# 32u4_macropad.net
KiCad netlist of a schematic drawn in EAGLE
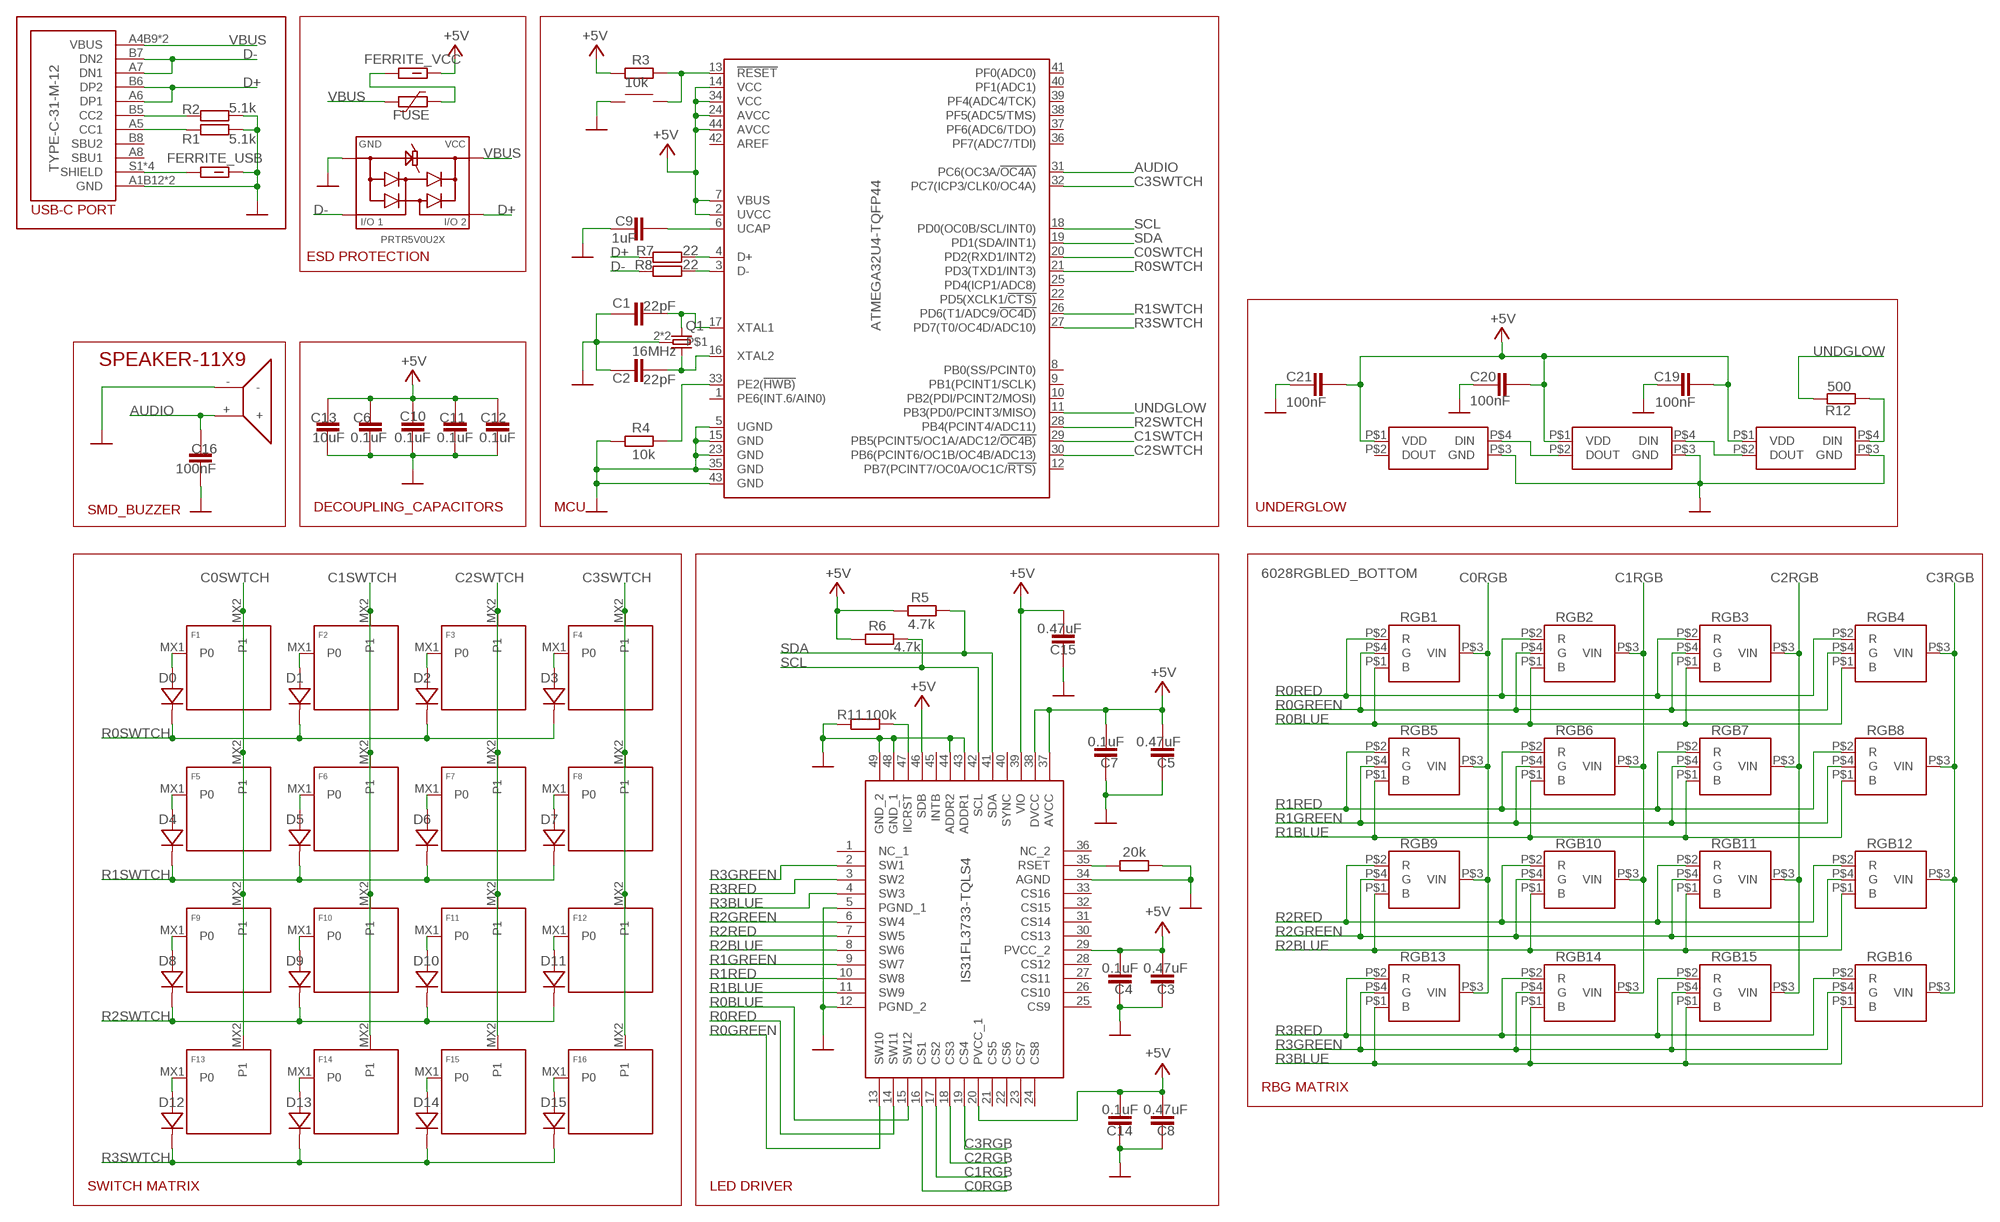
[diagram p0: schematic, sheet 1]

(export (version "E")
  (design (tool "Eeschema 10.0.6"))
  (components
    (comp (ref "C1")
      (value "22pF")
      (footprint "eagle-import:C0603")
      (libsource (lib "eagle-import") (part "CAPACITOR-0603"))
    )
    (comp (ref "C2")
      (value "22pF")
      (footprint "eagle-import:C0603")
      (libsource (lib "eagle-import") (part "CAPACITOR-0603"))
    )
    (comp (ref "C3")
      (value "0.47uF")
      (footprint "eagle-import:C0603")
      (libsource (lib "eagle-import") (part "CAPACITOR-0603"))
    )
    (comp (ref "C4")
      (value "0.1uF")
      (footprint "eagle-import:C0603")
      (libsource (lib "eagle-import") (part "CAPACITOR-0603"))
    )
    (comp (ref "C5")
      (value "0.47uF")
      (footprint "eagle-import:C0603")
      (libsource (lib "eagle-import") (part "CAPACITOR-0603"))
    )
    (comp (ref "C6")
      (value "0.1uF")
      (footprint "eagle-import:C0603")
      (libsource (lib "eagle-import") (part "CAPACITOR-0603"))
    )
    (comp (ref "C7")
      (value "0.1uF")
      (footprint "eagle-import:C0603")
      (libsource (lib "eagle-import") (part "CAPACITOR-0603"))
    )
    (comp (ref "C8")
      (value "0.47uF")
      (footprint "eagle-import:C0603")
      (libsource (lib "eagle-import") (part "CAPACITOR-0603"))
    )
    (comp (ref "C9")
      (value "1uF")
      (footprint "eagle-import:C0603")
      (libsource (lib "eagle-import") (part "CAPACITOR-0603"))
    )
    (comp (ref "C10")
      (value "0.1uF")
      (footprint "eagle-import:C0603")
      (libsource (lib "eagle-import") (part "CAPACITOR-0603"))
    )
    (comp (ref "C11")
      (value "0.1uF")
      (footprint "eagle-import:C0603")
      (libsource (lib "eagle-import") (part "CAPACITOR-0603"))
    )
    (comp (ref "C12")
      (value "0.1uF")
      (footprint "eagle-import:C0603")
      (libsource (lib "eagle-import") (part "CAPACITOR-0603"))
    )
    (comp (ref "C13")
      (value "10uF")
      (footprint "eagle-import:C0603")
      (libsource (lib "eagle-import") (part "CAPACITOR-0603"))
    )
    (comp (ref "C14")
      (value "0.1uF")
      (footprint "eagle-import:C0603")
      (libsource (lib "eagle-import") (part "CAPACITOR-0603"))
    )
    (comp (ref "C15")
      (value "0.47uF")
      (footprint "eagle-import:C0603")
      (libsource (lib "eagle-import") (part "CAPACITOR-0603"))
    )
    (comp (ref "C16")
      (value "100nF")
      (footprint "eagle-import:C0603")
      (libsource (lib "eagle-import") (part "CAPACITOR-0603"))
    )
    (comp (ref "C19")
      (value "100nF")
      (footprint "eagle-import:C0603")
      (libsource (lib "eagle-import") (part "CAPACITOR-0603"))
    )
    (comp (ref "C20")
      (value "100nF")
      (footprint "eagle-import:C0603")
      (libsource (lib "eagle-import") (part "CAPACITOR-0603"))
    )
    (comp (ref "C21")
      (value "100nF")
      (footprint "eagle-import:C0603")
      (libsource (lib "eagle-import") (part "CAPACITOR-0603"))
    )
    (comp (ref "D0")
      (value "DIODE-SOD-123")
      (footprint "eagle-import:SOD-123")
      (libsource (lib "eagle-import") (part "DIODE-SOD-123"))
    )
    (comp (ref "D1")
      (value "DIODE-SOD-123")
      (footprint "eagle-import:SOD-123")
      (libsource (lib "eagle-import") (part "DIODE-SOD-123"))
    )
    (comp (ref "D2")
      (value "DIODE-SOD-123")
      (footprint "eagle-import:SOD-123")
      (libsource (lib "eagle-import") (part "DIODE-SOD-123"))
    )
    (comp (ref "D3")
      (value "DIODE-SOD-123")
      (footprint "eagle-import:SOD-123")
      (libsource (lib "eagle-import") (part "DIODE-SOD-123"))
    )
    (comp (ref "D4")
      (value "DIODE-SOD-123")
      (footprint "eagle-import:SOD-123")
      (libsource (lib "eagle-import") (part "DIODE-SOD-123"))
    )
    (comp (ref "D5")
      (value "DIODE-SOD-123")
      (footprint "eagle-import:SOD-123")
      (libsource (lib "eagle-import") (part "DIODE-SOD-123"))
    )
    (comp (ref "D6")
      (value "DIODE-SOD-123")
      (footprint "eagle-import:SOD-123")
      (libsource (lib "eagle-import") (part "DIODE-SOD-123"))
    )
    (comp (ref "D7")
      (value "DIODE-SOD-123")
      (footprint "eagle-import:SOD-123")
      (libsource (lib "eagle-import") (part "DIODE-SOD-123"))
    )
    (comp (ref "D8")
      (value "DIODE-SOD-123")
      (footprint "eagle-import:SOD-123")
      (libsource (lib "eagle-import") (part "DIODE-SOD-123"))
    )
    (comp (ref "D9")
      (value "DIODE-SOD-123")
      (footprint "eagle-import:SOD-123")
      (libsource (lib "eagle-import") (part "DIODE-SOD-123"))
    )
    (comp (ref "D10")
      (value "DIODE-SOD-123")
      (footprint "eagle-import:SOD-123")
      (libsource (lib "eagle-import") (part "DIODE-SOD-123"))
    )
    (comp (ref "D11")
      (value "DIODE-SOD-123")
      (footprint "eagle-import:SOD-123")
      (libsource (lib "eagle-import") (part "DIODE-SOD-123"))
    )
    (comp (ref "D12")
      (value "DIODE-SOD-123")
      (footprint "eagle-import:SOD-123")
      (libsource (lib "eagle-import") (part "DIODE-SOD-123"))
    )
    (comp (ref "D13")
      (value "DIODE-SOD-123")
      (footprint "eagle-import:SOD-123")
      (libsource (lib "eagle-import") (part "DIODE-SOD-123"))
    )
    (comp (ref "D14")
      (value "DIODE-SOD-123")
      (footprint "eagle-import:SOD-123")
      (libsource (lib "eagle-import") (part "DIODE-SOD-123"))
    )
    (comp (ref "D15")
      (value "DIODE-SOD-123")
      (footprint "eagle-import:SOD-123")
      (libsource (lib "eagle-import") (part "DIODE-SOD-123"))
    )
    (comp (ref "DRIVER")
      (value "IS31FL3733-TQLS4")
      (footprint "eagle-import:QFP50P900X900X120-49N")
      (fields (field (name "MOUSER_PART_NUMBER") "870-IS31FL3733-TQLS4"))
      (libsource (lib "eagle-import") (part "IS31FL3733-TQLS4"))
    )
    (comp (ref "F1")
      (value "KEYSWITCH-PLAIN-MX-1U")
      (footprint "eagle-import:MX-1U")
      (libsource (lib "eagle-import") (part "KEYSWITCH-PLAIN-MX-1U"))
    )
    (comp (ref "F2")
      (value "KEYSWITCH-PLAIN-MX-1U")
      (footprint "eagle-import:MX-1U")
      (libsource (lib "eagle-import") (part "KEYSWITCH-PLAIN-MX-1U"))
    )
    (comp (ref "F3")
      (value "KEYSWITCH-PLAIN-MX-1U")
      (footprint "eagle-import:MX-1U")
      (libsource (lib "eagle-import") (part "KEYSWITCH-PLAIN-MX-1U"))
    )
    (comp (ref "F4")
      (value "KEYSWITCH-PLAIN-MX-1U")
      (footprint "eagle-import:MX-1U")
      (libsource (lib "eagle-import") (part "KEYSWITCH-PLAIN-MX-1U"))
    )
    (comp (ref "F5")
      (value "KEYSWITCH-PLAIN-MX-1U")
      (footprint "eagle-import:MX-1U")
      (libsource (lib "eagle-import") (part "KEYSWITCH-PLAIN-MX-1U"))
    )
    (comp (ref "F6")
      (value "KEYSWITCH-PLAIN-MX-1U")
      (footprint "eagle-import:MX-1U")
      (libsource (lib "eagle-import") (part "KEYSWITCH-PLAIN-MX-1U"))
    )
    (comp (ref "F7")
      (value "KEYSWITCH-PLAIN-MX-1U")
      (footprint "eagle-import:MX-1U")
      (libsource (lib "eagle-import") (part "KEYSWITCH-PLAIN-MX-1U"))
    )
    (comp (ref "F8")
      (value "KEYSWITCH-PLAIN-MX-1U")
      (footprint "eagle-import:MX-1U")
      (libsource (lib "eagle-import") (part "KEYSWITCH-PLAIN-MX-1U"))
    )
    (comp (ref "F9")
      (value "KEYSWITCH-PLAIN-MX-1U")
      (footprint "eagle-import:MX-1U")
      (libsource (lib "eagle-import") (part "KEYSWITCH-PLAIN-MX-1U"))
    )
    (comp (ref "F10")
      (value "KEYSWITCH-PLAIN-MX-1U")
      (footprint "eagle-import:MX-1U")
      (libsource (lib "eagle-import") (part "KEYSWITCH-PLAIN-MX-1U"))
    )
    (comp (ref "F11")
      (value "KEYSWITCH-PLAIN-MX-1U")
      (footprint "eagle-import:MX-1U")
      (libsource (lib "eagle-import") (part "KEYSWITCH-PLAIN-MX-1U"))
    )
    (comp (ref "F12")
      (value "KEYSWITCH-PLAIN-MX-1U")
      (footprint "eagle-import:MX-1U")
      (libsource (lib "eagle-import") (part "KEYSWITCH-PLAIN-MX-1U"))
    )
    (comp (ref "F13")
      (value "KEYSWITCH-PLAIN-MX-1U")
      (footprint "eagle-import:MX-1U")
      (libsource (lib "eagle-import") (part "KEYSWITCH-PLAIN-MX-1U"))
    )
    (comp (ref "F14")
      (value "KEYSWITCH-PLAIN-MX-1U")
      (footprint "eagle-import:MX-1U")
      (libsource (lib "eagle-import") (part "KEYSWITCH-PLAIN-MX-1U"))
    )
    (comp (ref "F15")
      (value "KEYSWITCH-PLAIN-MX-1U")
      (footprint "eagle-import:MX-1U")
      (libsource (lib "eagle-import") (part "KEYSWITCH-PLAIN-MX-1U"))
    )
    (comp (ref "F16")
      (value "KEYSWITCH-PLAIN-MX-1U")
      (footprint "eagle-import:MX-1U")
      (libsource (lib "eagle-import") (part "KEYSWITCH-PLAIN-MX-1U"))
    )
    (comp (ref "FERRITE_USB")
      (value "FERRITE_BEAD")
      (footprint "eagle-import:BEADC1608X95N")
      (libsource (lib "eagle-import") (part "FBCHIP-0603(1608-METRIC)"))
    )
    (comp (ref "FERRITE_VCC")
      (value "FERRITE_BEAD")
      (footprint "eagle-import:BEADC1608X95N")
      (libsource (lib "eagle-import") (part "FBCHIP-0603(1608-METRIC)"))
    )
    (comp (ref "FUSE")
      (value "0603L050")
      (footprint "eagle-import:0603L")
      (fields (field (name "MF") "Littelfuse"))
      (libsource (lib "eagle-import") (part "?0603L050"))
    )
    (comp (ref "J1")
      (value "TYPE-C-31-M-12")
      (footprint "eagle-import:HRO_TYPE-C-31-M-12")
      (fields (field (name "MF") "HRO Electronics Co., Ltd."))
      (libsource (lib "eagle-import") (part "TYPE-C-31-M-12"))
    )
    (comp (ref "MCU")
      (value "ATMEGA32U4-TQFP44")
      (footprint "eagle-import:TQFP44-0.8-9.6X9.6MM")
      (fields (field (name "MPN") "ATMEGA32U4"))
      (libsource (lib "eagle-import") (part "MCU-ATMEGA32U4-AU(TQFP44)"))
    )
    (comp (ref "Q1")
      (value "16MHz")
      (footprint "eagle-import:2.0X1.6_KX-5")
      (libsource (lib "eagle-import") (part "KX-5"))
    )
    (comp (ref "R1")
      (value "5.1k")
      (footprint "eagle-import:R0603")
      (libsource (lib "eagle-import") (part "RESISTOR-0603"))
    )
    (comp (ref "R2")
      (value "5.1k")
      (footprint "eagle-import:R0603")
      (libsource (lib "eagle-import") (part "RESISTOR-0603"))
    )
    (comp (ref "R3")
      (value "10k")
      (footprint "eagle-import:R0603")
      (libsource (lib "eagle-import") (part "RESISTOR-0603"))
    )
    (comp (ref "R4")
      (value "10k")
      (footprint "eagle-import:R0603")
      (libsource (lib "eagle-import") (part "RESISTOR-0603"))
    )
    (comp (ref "R5")
      (value "4.7k")
      (footprint "eagle-import:R0603")
      (libsource (lib "eagle-import") (part "RESISTOR-0603"))
    )
    (comp (ref "R6")
      (value "4.7k")
      (footprint "eagle-import:R0603")
      (libsource (lib "eagle-import") (part "RESISTOR-0603"))
    )
    (comp (ref "R7")
      (value "22")
      (footprint "eagle-import:R0603")
      (libsource (lib "eagle-import") (part "RESISTOR-0603"))
    )
    (comp (ref "R8")
      (value "22")
      (footprint "eagle-import:R0603")
      (libsource (lib "eagle-import") (part "RESISTOR-0603"))
    )
    (comp (ref "R11")
      (value "100k")
      (footprint "eagle-import:R0603")
      (libsource (lib "eagle-import") (part "RESISTOR-0603"))
    )
    (comp (ref "R12")
      (value "500")
      (footprint "eagle-import:R0603")
      (libsource (lib "eagle-import") (part "RESISTOR-0603"))
    )
    (comp (ref "RESET")
      (value "20k")
      (footprint "eagle-import:R0603")
      (libsource (lib "eagle-import") (part "RESISTOR-0603"))
    )
    (comp (ref "RGB1")
      (value "6028RGBLED_BOTTOM")
      (footprint "eagle-import:6028RGBLED_BOTTOM")
      (libsource (lib "eagle-import") (part "6028RGBLED_BOTTOM"))
    )
    (comp (ref "RGB2")
      (value "6028RGBLED_BOTTOM")
      (footprint "eagle-import:6028RGBLED_BOTTOM")
      (libsource (lib "eagle-import") (part "6028RGBLED_BOTTOM"))
    )
    (comp (ref "RGB3")
      (value "6028RGBLED_BOTTOM")
      (footprint "eagle-import:6028RGBLED_BOTTOM")
      (libsource (lib "eagle-import") (part "6028RGBLED_BOTTOM"))
    )
    (comp (ref "RGB4")
      (value "6028RGBLED_BOTTOM")
      (footprint "eagle-import:6028RGBLED_BOTTOM")
      (libsource (lib "eagle-import") (part "6028RGBLED_BOTTOM"))
    )
    (comp (ref "RGB5")
      (value "6028RGBLED_BOTTOM")
      (footprint "eagle-import:6028RGBLED_BOTTOM")
      (libsource (lib "eagle-import") (part "6028RGBLED_BOTTOM"))
    )
    (comp (ref "RGB6")
      (value "6028RGBLED_BOTTOM")
      (footprint "eagle-import:6028RGBLED_BOTTOM")
      (libsource (lib "eagle-import") (part "6028RGBLED_BOTTOM"))
    )
    (comp (ref "RGB7")
      (value "6028RGBLED_BOTTOM")
      (footprint "eagle-import:6028RGBLED_BOTTOM")
      (libsource (lib "eagle-import") (part "6028RGBLED_BOTTOM"))
    )
    (comp (ref "RGB8")
      (value "6028RGBLED_BOTTOM")
      (footprint "eagle-import:6028RGBLED_BOTTOM")
      (libsource (lib "eagle-import") (part "6028RGBLED_BOTTOM"))
    )
    (comp (ref "RGB9")
      (value "6028RGBLED_BOTTOM")
      (footprint "eagle-import:6028RGBLED_BOTTOM")
      (libsource (lib "eagle-import") (part "6028RGBLED_BOTTOM"))
    )
    (comp (ref "RGB10")
      (value "6028RGBLED_BOTTOM")
      (footprint "eagle-import:6028RGBLED_BOTTOM")
      (libsource (lib "eagle-import") (part "6028RGBLED_BOTTOM"))
    )
    (comp (ref "RGB11")
      (value "6028RGBLED_BOTTOM")
      (footprint "eagle-import:6028RGBLED_BOTTOM")
      (libsource (lib "eagle-import") (part "6028RGBLED_BOTTOM"))
    )
    (comp (ref "RGB12")
      (value "6028RGBLED_BOTTOM")
      (footprint "eagle-import:6028RGBLED_BOTTOM")
      (libsource (lib "eagle-import") (part "6028RGBLED_BOTTOM"))
    )
    (comp (ref "RGB13")
      (value "6028RGBLED_BOTTOM")
      (footprint "eagle-import:6028RGBLED_BOTTOM")
      (libsource (lib "eagle-import") (part "6028RGBLED_BOTTOM"))
    )
    (comp (ref "RGB14")
      (value "6028RGBLED_BOTTOM")
      (footprint "eagle-import:6028RGBLED_BOTTOM")
      (libsource (lib "eagle-import") (part "6028RGBLED_BOTTOM"))
    )
    (comp (ref "RGB15")
      (value "6028RGBLED_BOTTOM")
      (footprint "eagle-import:6028RGBLED_BOTTOM")
      (libsource (lib "eagle-import") (part "6028RGBLED_BOTTOM"))
    )
    (comp (ref "RGB16")
      (value "6028RGBLED_BOTTOM")
      (footprint "eagle-import:6028RGBLED_BOTTOM")
      (libsource (lib "eagle-import") (part "6028RGBLED_BOTTOM"))
    )
    (comp (ref "SP1")
      (value "SPEAKER-11X9")
      (footprint "eagle-import:AST1109MLTRQ")
      (libsource (lib "eagle-import") (part "SPEAKER-SMD-11X9"))
    )
    (comp (ref "SW2")
      (value "SWITCH-SMD-EVP-BB2A9B00")
      (footprint "eagle-import:SWITCH-SMD-EVP-BB2A9B00")
      (libsource (lib "eagle-import") (part "SWITCH-SMD-EVP-BB2A9B00"))
    )
    (comp (ref "U$1")
      (value "PRTR5V0U2X")
      (footprint "eagle-import:PRTR5V0U2X")
      (libsource (lib "eagle-import") (part "PRTR5V0U2X"))
    )
    (comp (ref "UGLOW1")
      (value "SK6812MINI-E")
      (footprint "eagle-import:SK6812MINI-E")
      (libsource (lib "eagle-import") (part "SK6812MINI-E"))
    )
    (comp (ref "UGLOW2")
      (value "SK6812MINI-E")
      (footprint "eagle-import:SK6812MINI-E")
      (libsource (lib "eagle-import") (part "SK6812MINI-E"))
    )
    (comp (ref "UGLOW3")
      (value "SK6812MINI-E")
      (footprint "eagle-import:SK6812MINI-E")
      (libsource (lib "eagle-import") (part "SK6812MINI-E"))
    )
  )
  (nets
    (net (code "1") (name "+5V") (class "Default")
      (node (ref "C10") (pin "1") (pinfunction "1_1") (pintype "passive"))
      (node (ref "C11") (pin "1") (pinfunction "1_1") (pintype "passive"))
      (node (ref "C12") (pin "1") (pinfunction "1_1") (pintype "passive"))
      (node (ref "C13") (pin "1") (pinfunction "1_1") (pintype "passive"))
      (node (ref "C14") (pin "2") (pinfunction "2_2") (pintype "passive"))
      (node (ref "C15") (pin "2") (pinfunction "2_2") (pintype "passive"))
      (node (ref "C19") (pin "2") (pinfunction "2_2") (pintype "passive"))
      (node (ref "C20") (pin "2") (pinfunction "2_2") (pintype "passive"))
      (node (ref "C21") (pin "2") (pinfunction "2_2") (pintype "passive"))
      (node (ref "C3") (pin "2") (pinfunction "2_2") (pintype "passive"))
      (node (ref "C4") (pin "2") (pinfunction "2_2") (pintype "passive"))
      (node (ref "C5") (pin "2") (pinfunction "2_2") (pintype "passive"))
      (node (ref "C6") (pin "1") (pinfunction "1_1") (pintype "passive"))
      (node (ref "C7") (pin "2") (pinfunction "2_2") (pintype "passive"))
      (node (ref "C8") (pin "2") (pinfunction "2_2") (pintype "passive"))
      (node (ref "DRIVER") (pin "20") (pinfunction "PVCC_1_20") (pintype "bidirectional"))
      (node (ref "DRIVER") (pin "29") (pinfunction "PVCC_2_29") (pintype "bidirectional"))
      (node (ref "DRIVER") (pin "37") (pinfunction "AVCC_37") (pintype "bidirectional"))
      (node (ref "DRIVER") (pin "38") (pinfunction "DVCC_38") (pintype "bidirectional"))
      (node (ref "DRIVER") (pin "39") (pinfunction "VIO_39") (pintype "bidirectional"))
      (node (ref "DRIVER") (pin "46") (pinfunction "SDB_46") (pintype "bidirectional"))
      (node (ref "FERRITE_VCC") (pin "2") (pinfunction "2_2") (pintype "passive"))
      (node (ref "MCU") (pin "14") (pinfunction "VCC_14") (pintype "bidirectional"))
      (node (ref "MCU") (pin "2") (pinfunction "UVCC_2") (pintype "bidirectional"))
      (node (ref "MCU") (pin "24") (pinfunction "AVCC_24") (pintype "bidirectional"))
      (node (ref "MCU") (pin "34") (pinfunction "VCC_34") (pintype "bidirectional"))
      (node (ref "MCU") (pin "44") (pinfunction "AVCC_44") (pintype "bidirectional"))
      (node (ref "MCU") (pin "7") (pinfunction "VBUS_7") (pintype "bidirectional"))
      (node (ref "R3") (pin "1") (pinfunction "1_1") (pintype "passive"))
      (node (ref "R5") (pin "2") (pinfunction "2_2") (pintype "passive"))
      (node (ref "R6") (pin "2") (pinfunction "2_2") (pintype "passive"))
      (node (ref "UGLOW1") (pin "P$1") (pinfunction "VDD_P$1") (pintype "power_in"))
      (node (ref "UGLOW2") (pin "P$1") (pinfunction "VDD_P$1") (pintype "power_in"))
      (node (ref "UGLOW3") (pin "P$1") (pinfunction "VDD_P$1") (pintype "power_in"))
    )
    (net (code "2") (name "/AUDIO") (class "Default")
      (node (ref "C16") (pin "1") (pinfunction "1_1") (pintype "passive"))
      (node (ref "MCU") (pin "31") (pinfunction "PC6(OC3A/~{OC4A})_31") (pintype "bidirectional"))
      (node (ref "SP1") (pin "+") (pinfunction "+_+") (pintype "bidirectional"))
    )
    (net (code "3") (name "/C0RGB") (class "Default")
      (node (ref "DRIVER") (pin "16") (pinfunction "CS1_16") (pintype "bidirectional"))
      (node (ref "RGB1") (pin "P$3") (pinfunction "VIN_P$3") (pintype "power_in"))
      (node (ref "RGB13") (pin "P$3") (pinfunction "VIN_P$3") (pintype "power_in"))
      (node (ref "RGB5") (pin "P$3") (pinfunction "VIN_P$3") (pintype "power_in"))
      (node (ref "RGB9") (pin "P$3") (pinfunction "VIN_P$3") (pintype "power_in"))
    )
    (net (code "4") (name "/C0SWTCH") (class "Default")
      (node (ref "F1") (pin "MX2") (pinfunction "P1_MX2") (pintype "bidirectional"))
      (node (ref "F13") (pin "MX2") (pinfunction "P1_MX2") (pintype "bidirectional"))
      (node (ref "F5") (pin "MX2") (pinfunction "P1_MX2") (pintype "bidirectional"))
      (node (ref "F9") (pin "MX2") (pinfunction "P1_MX2") (pintype "bidirectional"))
      (node (ref "MCU") (pin "20") (pinfunction "PD2(RXD1/INT2)_20") (pintype "bidirectional"))
    )
    (net (code "5") (name "/C1RGB") (class "Default")
      (node (ref "DRIVER") (pin "17") (pinfunction "CS2_17") (pintype "bidirectional"))
      (node (ref "RGB10") (pin "P$3") (pinfunction "VIN_P$3") (pintype "power_in"))
      (node (ref "RGB14") (pin "P$3") (pinfunction "VIN_P$3") (pintype "power_in"))
      (node (ref "RGB2") (pin "P$3") (pinfunction "VIN_P$3") (pintype "power_in"))
      (node (ref "RGB6") (pin "P$3") (pinfunction "VIN_P$3") (pintype "power_in"))
    )
    (net (code "6") (name "/C1SWTCH") (class "Default")
      (node (ref "F10") (pin "MX2") (pinfunction "P1_MX2") (pintype "bidirectional"))
      (node (ref "F14") (pin "MX2") (pinfunction "P1_MX2") (pintype "bidirectional"))
      (node (ref "F2") (pin "MX2") (pinfunction "P1_MX2") (pintype "bidirectional"))
      (node (ref "F6") (pin "MX2") (pinfunction "P1_MX2") (pintype "bidirectional"))
      (node (ref "MCU") (pin "29") (pinfunction "PB5(PCINT5/OC1A/ADC12/~{OC4B})_29") (pintype "bidirectional"))
    )
    (net (code "7") (name "/C2RGB") (class "Default")
      (node (ref "DRIVER") (pin "18") (pinfunction "CS3_18") (pintype "bidirectional"))
      (node (ref "RGB11") (pin "P$3") (pinfunction "VIN_P$3") (pintype "power_in"))
      (node (ref "RGB15") (pin "P$3") (pinfunction "VIN_P$3") (pintype "power_in"))
      (node (ref "RGB3") (pin "P$3") (pinfunction "VIN_P$3") (pintype "power_in"))
      (node (ref "RGB7") (pin "P$3") (pinfunction "VIN_P$3") (pintype "power_in"))
    )
    (net (code "8") (name "/C2SWTCH") (class "Default")
      (node (ref "F11") (pin "MX2") (pinfunction "P1_MX2") (pintype "bidirectional"))
      (node (ref "F15") (pin "MX2") (pinfunction "P1_MX2") (pintype "bidirectional"))
      (node (ref "F3") (pin "MX2") (pinfunction "P1_MX2") (pintype "bidirectional"))
      (node (ref "F7") (pin "MX2") (pinfunction "P1_MX2") (pintype "bidirectional"))
      (node (ref "MCU") (pin "30") (pinfunction "PB6(PCINT6/OC1B/OC4B/ADC13)_30") (pintype "bidirectional"))
    )
    (net (code "9") (name "/C3RGB") (class "Default")
      (node (ref "DRIVER") (pin "19") (pinfunction "CS4_19") (pintype "bidirectional"))
      (node (ref "RGB12") (pin "P$3") (pinfunction "VIN_P$3") (pintype "power_in"))
      (node (ref "RGB16") (pin "P$3") (pinfunction "VIN_P$3") (pintype "power_in"))
      (node (ref "RGB4") (pin "P$3") (pinfunction "VIN_P$3") (pintype "power_in"))
      (node (ref "RGB8") (pin "P$3") (pinfunction "VIN_P$3") (pintype "power_in"))
    )
    (net (code "10") (name "/C3SWTCH") (class "Default")
      (node (ref "F12") (pin "MX2") (pinfunction "P1_MX2") (pintype "bidirectional"))
      (node (ref "F16") (pin "MX2") (pinfunction "P1_MX2") (pintype "bidirectional"))
      (node (ref "F4") (pin "MX2") (pinfunction "P1_MX2") (pintype "bidirectional"))
      (node (ref "F8") (pin "MX2") (pinfunction "P1_MX2") (pintype "bidirectional"))
      (node (ref "MCU") (pin "32") (pinfunction "PC7(ICP3/CLK0/OC4A)_32") (pintype "bidirectional"))
    )
    (net (code "11") (name "/D+") (class "Default")
      (node (ref "J1") (pin "A6") (pinfunction "DP1_A6") (pintype "bidirectional"))
      (node (ref "J1") (pin "B6") (pinfunction "DP2_B6") (pintype "bidirectional"))
      (node (ref "R7") (pin "1") (pinfunction "1_1") (pintype "passive"))
      (node (ref "U$1") (pin "3") (pinfunction "3_3") (pintype "bidirectional"))
    )
    (net (code "12") (name "/D-") (class "Default")
      (node (ref "J1") (pin "A7") (pinfunction "DN1_A7") (pintype "bidirectional"))
      (node (ref "J1") (pin "B7") (pinfunction "DN2_B7") (pintype "bidirectional"))
      (node (ref "R8") (pin "1") (pinfunction "1_1") (pintype "passive"))
      (node (ref "U$1") (pin "2") (pinfunction "2_2") (pintype "bidirectional"))
    )
    (net (code "13") (name "/N$24") (class "Default")
      (node (ref "FERRITE_USB") (pin "1") (pinfunction "1_1") (pintype "passive"))
      (node (ref "J1") (pin "A5") (pinfunction "CC1_A5") (pintype "bidirectional"))
      (node (ref "J1") (pin "B5") (pinfunction "CC2_B5") (pintype "bidirectional"))
      (node (ref "J1") (pin "S1") (pinfunction "SHIELD_S1") (pintype "passive"))
      (node (ref "J1") (pin "S2") (pinfunction "SHIELD_S2") (pintype "passive"))
      (node (ref "J1") (pin "S3") (pinfunction "SHIELD_S3") (pintype "passive"))
      (node (ref "J1") (pin "S4") (pinfunction "SHIELD_S4") (pintype "passive"))
      (node (ref "R1") (pin "2") (pinfunction "2_2") (pintype "passive"))
      (node (ref "R2") (pin "2") (pinfunction "2_2") (pintype "passive"))
    )
    (net (code "14") (name "/R0BLUE") (class "Default")
      (node (ref "DRIVER") (pin "15") (pinfunction "SW12_15") (pintype "bidirectional"))
      (node (ref "RGB1") (pin "P$1") (pinfunction "B_P$1") (pintype "bidirectional"))
      (node (ref "RGB2") (pin "P$1") (pinfunction "B_P$1") (pintype "bidirectional"))
      (node (ref "RGB3") (pin "P$1") (pinfunction "B_P$1") (pintype "bidirectional"))
      (node (ref "RGB4") (pin "P$1") (pinfunction "B_P$1") (pintype "bidirectional"))
    )
    (net (code "15") (name "/R0GREEN") (class "Default")
      (node (ref "DRIVER") (pin "13") (pinfunction "SW10_13") (pintype "bidirectional"))
      (node (ref "RGB1") (pin "P$4") (pinfunction "G_P$4") (pintype "output"))
      (node (ref "RGB2") (pin "P$4") (pinfunction "G_P$4") (pintype "output"))
      (node (ref "RGB3") (pin "P$4") (pinfunction "G_P$4") (pintype "output"))
      (node (ref "RGB4") (pin "P$4") (pinfunction "G_P$4") (pintype "output"))
    )
    (net (code "16") (name "/R0RED") (class "Default")
      (node (ref "DRIVER") (pin "14") (pinfunction "SW11_14") (pintype "bidirectional"))
      (node (ref "RGB1") (pin "P$2") (pinfunction "R_P$2") (pintype "power_in"))
      (node (ref "RGB2") (pin "P$2") (pinfunction "R_P$2") (pintype "power_in"))
      (node (ref "RGB3") (pin "P$2") (pinfunction "R_P$2") (pintype "power_in"))
      (node (ref "RGB4") (pin "P$2") (pinfunction "R_P$2") (pintype "power_in"))
    )
    (net (code "17") (name "/R0SWTCH") (class "Default")
      (node (ref "D0") (pin "C") (pinfunction "C_C") (pintype "passive"))
      (node (ref "D1") (pin "C") (pinfunction "C_C") (pintype "passive"))
      (node (ref "D2") (pin "C") (pinfunction "C_C") (pintype "passive"))
      (node (ref "D3") (pin "C") (pinfunction "C_C") (pintype "passive"))
      (node (ref "MCU") (pin "21") (pinfunction "PD3(TXD1/INT3)_21") (pintype "bidirectional"))
    )
    (net (code "18") (name "/R1BLUE") (class "Default")
      (node (ref "DRIVER") (pin "11") (pinfunction "SW9_11") (pintype "bidirectional"))
      (node (ref "RGB5") (pin "P$1") (pinfunction "B_P$1") (pintype "bidirectional"))
      (node (ref "RGB6") (pin "P$1") (pinfunction "B_P$1") (pintype "bidirectional"))
      (node (ref "RGB7") (pin "P$1") (pinfunction "B_P$1") (pintype "bidirectional"))
      (node (ref "RGB8") (pin "P$1") (pinfunction "B_P$1") (pintype "bidirectional"))
    )
    (net (code "19") (name "/R1GREEN") (class "Default")
      (node (ref "DRIVER") (pin "9") (pinfunction "SW7_9") (pintype "bidirectional"))
      (node (ref "RGB5") (pin "P$4") (pinfunction "G_P$4") (pintype "output"))
      (node (ref "RGB6") (pin "P$4") (pinfunction "G_P$4") (pintype "output"))
      (node (ref "RGB7") (pin "P$4") (pinfunction "G_P$4") (pintype "output"))
      (node (ref "RGB8") (pin "P$4") (pinfunction "G_P$4") (pintype "output"))
    )
    (net (code "20") (name "/R1RED") (class "Default")
      (node (ref "DRIVER") (pin "10") (pinfunction "SW8_10") (pintype "bidirectional"))
      (node (ref "RGB5") (pin "P$2") (pinfunction "R_P$2") (pintype "power_in"))
      (node (ref "RGB6") (pin "P$2") (pinfunction "R_P$2") (pintype "power_in"))
      (node (ref "RGB7") (pin "P$2") (pinfunction "R_P$2") (pintype "power_in"))
      (node (ref "RGB8") (pin "P$2") (pinfunction "R_P$2") (pintype "power_in"))
    )
    (net (code "21") (name "/R1SWTCH") (class "Default")
      (node (ref "D4") (pin "C") (pinfunction "C_C") (pintype "passive"))
      (node (ref "D5") (pin "C") (pinfunction "C_C") (pintype "passive"))
      (node (ref "D6") (pin "C") (pinfunction "C_C") (pintype "passive"))
      (node (ref "D7") (pin "C") (pinfunction "C_C") (pintype "passive"))
      (node (ref "MCU") (pin "26") (pinfunction "PD6(T1/ADC9/~{OC4D})_26") (pintype "bidirectional"))
    )
    (net (code "22") (name "/R2BLUE") (class "Default")
      (node (ref "DRIVER") (pin "8") (pinfunction "SW6_8") (pintype "bidirectional"))
      (node (ref "RGB10") (pin "P$1") (pinfunction "B_P$1") (pintype "bidirectional"))
      (node (ref "RGB11") (pin "P$1") (pinfunction "B_P$1") (pintype "bidirectional"))
      (node (ref "RGB12") (pin "P$1") (pinfunction "B_P$1") (pintype "bidirectional"))
      (node (ref "RGB9") (pin "P$1") (pinfunction "B_P$1") (pintype "bidirectional"))
    )
    (net (code "23") (name "/R2GREEN") (class "Default")
      (node (ref "DRIVER") (pin "6") (pinfunction "SW4_6") (pintype "bidirectional"))
      (node (ref "RGB10") (pin "P$4") (pinfunction "G_P$4") (pintype "output"))
      (node (ref "RGB11") (pin "P$4") (pinfunction "G_P$4") (pintype "output"))
      (node (ref "RGB12") (pin "P$4") (pinfunction "G_P$4") (pintype "output"))
      (node (ref "RGB9") (pin "P$4") (pinfunction "G_P$4") (pintype "output"))
    )
    (net (code "24") (name "/R2RED") (class "Default")
      (node (ref "DRIVER") (pin "7") (pinfunction "SW5_7") (pintype "bidirectional"))
      (node (ref "RGB10") (pin "P$2") (pinfunction "R_P$2") (pintype "power_in"))
      (node (ref "RGB11") (pin "P$2") (pinfunction "R_P$2") (pintype "power_in"))
      (node (ref "RGB12") (pin "P$2") (pinfunction "R_P$2") (pintype "power_in"))
      (node (ref "RGB9") (pin "P$2") (pinfunction "R_P$2") (pintype "power_in"))
    )
    (net (code "25") (name "/R2SWTCH") (class "Default")
      (node (ref "D10") (pin "C") (pinfunction "C_C") (pintype "passive"))
      (node (ref "D11") (pin "C") (pinfunction "C_C") (pintype "passive"))
      (node (ref "D8") (pin "C") (pinfunction "C_C") (pintype "passive"))
      (node (ref "D9") (pin "C") (pinfunction "C_C") (pintype "passive"))
      (node (ref "MCU") (pin "28") (pinfunction "PB4(PCINT4/ADC11)_28") (pintype "bidirectional"))
    )
    (net (code "26") (name "/R3BLUE") (class "Default")
      (node (ref "DRIVER") (pin "4") (pinfunction "SW3_4") (pintype "bidirectional"))
      (node (ref "RGB13") (pin "P$1") (pinfunction "B_P$1") (pintype "bidirectional"))
      (node (ref "RGB14") (pin "P$1") (pinfunction "B_P$1") (pintype "bidirectional"))
      (node (ref "RGB15") (pin "P$1") (pinfunction "B_P$1") (pintype "bidirectional"))
      (node (ref "RGB16") (pin "P$1") (pinfunction "B_P$1") (pintype "bidirectional"))
    )
    (net (code "27") (name "/R3GREEN") (class "Default")
      (node (ref "DRIVER") (pin "2") (pinfunction "SW1_2") (pintype "bidirectional"))
      (node (ref "RGB13") (pin "P$4") (pinfunction "G_P$4") (pintype "output"))
      (node (ref "RGB14") (pin "P$4") (pinfunction "G_P$4") (pintype "output"))
      (node (ref "RGB15") (pin "P$4") (pinfunction "G_P$4") (pintype "output"))
      (node (ref "RGB16") (pin "P$4") (pinfunction "G_P$4") (pintype "output"))
    )
    (net (code "28") (name "/R3RED") (class "Default")
      (node (ref "DRIVER") (pin "3") (pinfunction "SW2_3") (pintype "bidirectional"))
      (node (ref "RGB13") (pin "P$2") (pinfunction "R_P$2") (pintype "power_in"))
      (node (ref "RGB14") (pin "P$2") (pinfunction "R_P$2") (pintype "power_in"))
      (node (ref "RGB15") (pin "P$2") (pinfunction "R_P$2") (pintype "power_in"))
      (node (ref "RGB16") (pin "P$2") (pinfunction "R_P$2") (pintype "power_in"))
    )
    (net (code "29") (name "/R3SWTCH") (class "Default")
      (node (ref "D12") (pin "C") (pinfunction "C_C") (pintype "passive"))
      (node (ref "D13") (pin "C") (pinfunction "C_C") (pintype "passive"))
      (node (ref "D14") (pin "C") (pinfunction "C_C") (pintype "passive"))
      (node (ref "D15") (pin "C") (pinfunction "C_C") (pintype "passive"))
      (node (ref "MCU") (pin "27") (pinfunction "PD7(T0/OC4D/ADC10)_27") (pintype "bidirectional"))
    )
    (net (code "30") (name "/SCL") (class "Default")
      (node (ref "DRIVER") (pin "42") (pinfunction "SCL_42") (pintype "bidirectional"))
      (node (ref "MCU") (pin "18") (pinfunction "PD0(OC0B/SCL/INT0)_18") (pintype "bidirectional"))
      (node (ref "R6") (pin "1") (pinfunction "1_1") (pintype "passive"))
    )
    (net (code "31") (name "/SDA") (class "Default")
      (node (ref "DRIVER") (pin "41") (pinfunction "SDA_41") (pintype "bidirectional"))
      (node (ref "MCU") (pin "19") (pinfunction "PD1(SDA/INT1)_19") (pintype "bidirectional"))
      (node (ref "R5") (pin "1") (pinfunction "1_1") (pintype "passive"))
    )
    (net (code "32") (name "/UNDGLOW") (class "Default")
      (node (ref "MCU") (pin "11") (pinfunction "PB3(PD0/PCINT3/MISO)_11") (pintype "bidirectional"))
      (node (ref "R12") (pin "2") (pinfunction "2_2") (pintype "passive"))
    )
    (net (code "33") (name "/VBUS") (class "Default")
      (node (ref "FUSE") (pin "2") (pinfunction "2_2") (pintype "passive"))
      (node (ref "J1") (pin "A4B9") (pinfunction "VBUS_A4B9") (pintype "power_in"))
      (node (ref "J1") (pin "B4A9") (pinfunction "VBUS_B4A9") (pintype "power_in"))
      (node (ref "U$1") (pin "4") (pinfunction "4_4") (pintype "bidirectional"))
    )
    (net (code "34") (name "GND") (class "Default")
      (node (ref "C1") (pin "1") (pinfunction "1_1") (pintype "passive"))
      (node (ref "C10") (pin "2") (pinfunction "2_2") (pintype "passive"))
      (node (ref "C11") (pin "2") (pinfunction "2_2") (pintype "passive"))
      (node (ref "C12") (pin "2") (pinfunction "2_2") (pintype "passive"))
      (node (ref "C13") (pin "2") (pinfunction "2_2") (pintype "passive"))
      (node (ref "C14") (pin "1") (pinfunction "1_1") (pintype "passive"))
      (node (ref "C15") (pin "1") (pinfunction "1_1") (pintype "passive"))
      (node (ref "C16") (pin "2") (pinfunction "2_2") (pintype "passive"))
      (node (ref "C19") (pin "1") (pinfunction "1_1") (pintype "passive"))
      (node (ref "C2") (pin "1") (pinfunction "1_1") (pintype "passive"))
      (node (ref "C20") (pin "1") (pinfunction "1_1") (pintype "passive"))
      (node (ref "C21") (pin "1") (pinfunction "1_1") (pintype "passive"))
      (node (ref "C3") (pin "1") (pinfunction "1_1") (pintype "passive"))
      (node (ref "C4") (pin "1") (pinfunction "1_1") (pintype "passive"))
      (node (ref "C5") (pin "1") (pinfunction "1_1") (pintype "passive"))
      (node (ref "C6") (pin "2") (pinfunction "2_2") (pintype "passive"))
      (node (ref "C7") (pin "1") (pinfunction "1_1") (pintype "passive"))
      (node (ref "C8") (pin "1") (pinfunction "1_1") (pintype "passive"))
      (node (ref "C9") (pin "1") (pinfunction "1_1") (pintype "passive"))
      (node (ref "DRIVER") (pin "12") (pinfunction "PGND_2_12") (pintype "bidirectional"))
      (node (ref "DRIVER") (pin "34") (pinfunction "AGND_34") (pintype "bidirectional"))
      (node (ref "DRIVER") (pin "43") (pinfunction "ADDR1_43") (pintype "bidirectional"))
      (node (ref "DRIVER") (pin "44") (pinfunction "ADDR2_44") (pintype "bidirectional"))
      (node (ref "DRIVER") (pin "48") (pinfunction "GND_1_48") (pintype "bidirectional"))
      (node (ref "DRIVER") (pin "49") (pinfunction "GND_2_49") (pintype "bidirectional"))
      (node (ref "DRIVER") (pin "5") (pinfunction "PGND_1_5") (pintype "bidirectional"))
      (node (ref "FERRITE_USB") (pin "2") (pinfunction "2_2") (pintype "passive"))
      (node (ref "J1") (pin "A1B12") (pinfunction "GND_A1B12") (pintype "power_in"))
      (node (ref "J1") (pin "B1A12") (pinfunction "GND_B1A12") (pintype "power_in"))
      (node (ref "MCU") (pin "15") (pinfunction "GND_15") (pintype "bidirectional"))
      (node (ref "MCU") (pin "23") (pinfunction "GND_23") (pintype "bidirectional"))
      (node (ref "MCU") (pin "35") (pinfunction "GND_35") (pintype "bidirectional"))
      (node (ref "MCU") (pin "43") (pinfunction "GND_43") (pintype "bidirectional"))
      (node (ref "MCU") (pin "5") (pinfunction "UGND_5") (pintype "bidirectional"))
      (node (ref "Q1") (pin "2") (pinfunction "P$1_2") (pintype "power_in"))
      (node (ref "Q1") (pin "4") (pinfunction "P$1_4") (pintype "power_in"))
      (node (ref "R1") (pin "1") (pinfunction "1_1") (pintype "passive"))
      (node (ref "R11") (pin "1") (pinfunction "1_1") (pintype "passive"))
      (node (ref "R2") (pin "1") (pinfunction "1_1") (pintype "passive"))
      (node (ref "R4") (pin "1") (pinfunction "1_1") (pintype "passive"))
      (node (ref "RESET") (pin "2") (pinfunction "2_2") (pintype "passive"))
      (node (ref "SP1") (pin "-") (pinfunction "-_-") (pintype "bidirectional"))
      (node (ref "SW2") (pin "A@1") (pinfunction "1_A@1") (pintype "passive"))
      (node (ref "SW2") (pin "A@2") (pinfunction "1_A@2") (pintype "passive"))
      (node (ref "U$1") (pin "1") (pinfunction "1_1") (pintype "bidirectional"))
      (node (ref "UGLOW1") (pin "P$3") (pinfunction "GND_P$3") (pintype "bidirectional"))
      (node (ref "UGLOW2") (pin "P$3") (pinfunction "GND_P$3") (pintype "bidirectional"))
      (node (ref "UGLOW3") (pin "P$3") (pinfunction "GND_P$3") (pintype "bidirectional"))
    )
    (net (code "35") (name "Net-(DRIVER-IICRST)") (class "Default")
      (node (ref "DRIVER") (pin "47") (pinfunction "IICRST_47") (pintype "bidirectional"))
      (node (ref "R11") (pin "2") (pinfunction "2_2") (pintype "passive"))
    )
    (net (code "36") (name "Net-(DRIVER-RSET)") (class "Default")
      (node (ref "DRIVER") (pin "35") (pinfunction "RSET_35") (pintype "bidirectional"))
      (node (ref "RESET") (pin "1") (pinfunction "1_1") (pintype "passive"))
    )
    (net (code "37") (name "Net-(F1-P0)") (class "Default")
      (node (ref "D0") (pin "A") (pinfunction "A_A") (pintype "passive"))
      (node (ref "F1") (pin "MX1") (pinfunction "P0_MX1") (pintype "bidirectional"))
    )
    (net (code "38") (name "Net-(F2-P0)") (class "Default")
      (node (ref "D1") (pin "A") (pinfunction "A_A") (pintype "passive"))
      (node (ref "F2") (pin "MX1") (pinfunction "P0_MX1") (pintype "bidirectional"))
    )
    (net (code "39") (name "Net-(F3-P0)") (class "Default")
      (node (ref "D2") (pin "A") (pinfunction "A_A") (pintype "passive"))
      (node (ref "F3") (pin "MX1") (pinfunction "P0_MX1") (pintype "bidirectional"))
    )
    (net (code "40") (name "Net-(F4-P0)") (class "Default")
      (node (ref "D3") (pin "A") (pinfunction "A_A") (pintype "passive"))
      (node (ref "F4") (pin "MX1") (pinfunction "P0_MX1") (pintype "bidirectional"))
    )
    (net (code "41") (name "Net-(F5-P0)") (class "Default")
      (node (ref "D4") (pin "A") (pinfunction "A_A") (pintype "passive"))
      (node (ref "F5") (pin "MX1") (pinfunction "P0_MX1") (pintype "bidirectional"))
    )
    (net (code "42") (name "Net-(F6-P0)") (class "Default")
      (node (ref "D5") (pin "A") (pinfunction "A_A") (pintype "passive"))
      (node (ref "F6") (pin "MX1") (pinfunction "P0_MX1") (pintype "bidirectional"))
    )
    (net (code "43") (name "Net-(F7-P0)") (class "Default")
      (node (ref "D6") (pin "A") (pinfunction "A_A") (pintype "passive"))
      (node (ref "F7") (pin "MX1") (pinfunction "P0_MX1") (pintype "bidirectional"))
    )
    (net (code "44") (name "Net-(F8-P0)") (class "Default")
      (node (ref "D7") (pin "A") (pinfunction "A_A") (pintype "passive"))
      (node (ref "F8") (pin "MX1") (pinfunction "P0_MX1") (pintype "bidirectional"))
    )
    (net (code "45") (name "Net-(F9-P0)") (class "Default")
      (node (ref "D8") (pin "A") (pinfunction "A_A") (pintype "passive"))
      (node (ref "F9") (pin "MX1") (pinfunction "P0_MX1") (pintype "bidirectional"))
    )
    (net (code "46") (name "Net-(F10-P0)") (class "Default")
      (node (ref "D9") (pin "A") (pinfunction "A_A") (pintype "passive"))
      (node (ref "F10") (pin "MX1") (pinfunction "P0_MX1") (pintype "bidirectional"))
    )
    (net (code "47") (name "Net-(F11-P0)") (class "Default")
      (node (ref "D10") (pin "A") (pinfunction "A_A") (pintype "passive"))
      (node (ref "F11") (pin "MX1") (pinfunction "P0_MX1") (pintype "bidirectional"))
    )
    (net (code "48") (name "Net-(F12-P0)") (class "Default")
      (node (ref "D11") (pin "A") (pinfunction "A_A") (pintype "passive"))
      (node (ref "F12") (pin "MX1") (pinfunction "P0_MX1") (pintype "bidirectional"))
    )
    (net (code "49") (name "Net-(F13-P0)") (class "Default")
      (node (ref "D12") (pin "A") (pinfunction "A_A") (pintype "passive"))
      (node (ref "F13") (pin "MX1") (pinfunction "P0_MX1") (pintype "bidirectional"))
    )
    (net (code "50") (name "Net-(F14-P0)") (class "Default")
      (node (ref "D13") (pin "A") (pinfunction "A_A") (pintype "passive"))
      (node (ref "F14") (pin "MX1") (pinfunction "P0_MX1") (pintype "bidirectional"))
    )
    (net (code "51") (name "Net-(F15-P0)") (class "Default")
      (node (ref "D14") (pin "A") (pinfunction "A_A") (pintype "passive"))
      (node (ref "F15") (pin "MX1") (pinfunction "P0_MX1") (pintype "bidirectional"))
    )
    (net (code "52") (name "Net-(F16-P0)") (class "Default")
      (node (ref "D15") (pin "A") (pinfunction "A_A") (pintype "passive"))
      (node (ref "F16") (pin "MX1") (pinfunction "P0_MX1") (pintype "bidirectional"))
    )
    (net (code "53") (name "Net-(FERRITE_VCC-Pad1)") (class "Default")
      (node (ref "FERRITE_VCC") (pin "1") (pinfunction "1_1") (pintype "passive"))
      (node (ref "FUSE") (pin "1") (pinfunction "1_1") (pintype "passive"))
    )
    (net (code "54") (name "Net-(MCU-D+)") (class "Default")
      (node (ref "MCU") (pin "4") (pinfunction "D+_4") (pintype "bidirectional"))
      (node (ref "R7") (pin "2") (pinfunction "2_2") (pintype "passive"))
    )
    (net (code "55") (name "Net-(MCU-D-)") (class "Default")
      (node (ref "MCU") (pin "3") (pinfunction "D-_3") (pintype "bidirectional"))
      (node (ref "R8") (pin "2") (pinfunction "2_2") (pintype "passive"))
    )
    (net (code "56") (name "Net-(MCU-PE2(~{HWB}))") (class "Default")
      (node (ref "MCU") (pin "33") (pinfunction "PE2(~{HWB})_33") (pintype "bidirectional"))
      (node (ref "R4") (pin "2") (pinfunction "2_2") (pintype "passive"))
    )
    (net (code "57") (name "Net-(MCU-UCAP)") (class "Default")
      (node (ref "C9") (pin "2") (pinfunction "2_2") (pintype "passive"))
      (node (ref "MCU") (pin "6") (pinfunction "UCAP_6") (pintype "bidirectional"))
    )
    (net (code "58") (name "Net-(MCU-XTAL1)") (class "Default")
      (node (ref "C1") (pin "2") (pinfunction "2_2") (pintype "passive"))
      (node (ref "MCU") (pin "17") (pinfunction "XTAL1_17") (pintype "bidirectional"))
      (node (ref "Q1") (pin "1") (pinfunction "1_1") (pintype "passive"))
    )
    (net (code "59") (name "Net-(MCU-XTAL2)") (class "Default")
      (node (ref "C2") (pin "2") (pinfunction "2_2") (pintype "passive"))
      (node (ref "MCU") (pin "16") (pinfunction "XTAL2_16") (pintype "bidirectional"))
      (node (ref "Q1") (pin "3") (pinfunction "2_3") (pintype "passive"))
    )
    (net (code "60") (name "Net-(MCU-~{RESET})") (class "Default")
      (node (ref "MCU") (pin "13") (pinfunction "~{RESET}_13") (pintype "bidirectional"))
      (node (ref "R3") (pin "2") (pinfunction "2_2") (pintype "passive"))
      (node (ref "SW2") (pin "B@3") (pinfunction "2_B@3") (pintype "passive"))
      (node (ref "SW2") (pin "B@4") (pinfunction "2_B@4") (pintype "passive"))
    )
    (net (code "61") (name "Net-(UGLOW1-DIN)") (class "Default")
      (node (ref "UGLOW1") (pin "P$4") (pinfunction "DIN_P$4") (pintype "power_in"))
      (node (ref "UGLOW2") (pin "P$2") (pinfunction "DOUT_P$2") (pintype "output"))
    )
    (net (code "62") (name "Net-(UGLOW2-DIN)") (class "Default")
      (node (ref "UGLOW2") (pin "P$4") (pinfunction "DIN_P$4") (pintype "power_in"))
      (node (ref "UGLOW3") (pin "P$2") (pinfunction "DOUT_P$2") (pintype "output"))
    )
    (net (code "63") (name "Net-(UGLOW3-DIN)") (class "Default")
      (node (ref "R12") (pin "1") (pinfunction "1_1") (pintype "passive"))
      (node (ref "UGLOW3") (pin "P$4") (pinfunction "DIN_P$4") (pintype "power_in"))
    )
    (net (code "64") (name "unconnected-(DRIVER-CS5-Pad21)") (class "Default")
      (node (ref "DRIVER") (pin "21") (pinfunction "CS5_21") (pintype "bidirectional"))
    )
    (net (code "65") (name "unconnected-(DRIVER-CS6-Pad22)") (class "Default")
      (node (ref "DRIVER") (pin "22") (pinfunction "CS6_22") (pintype "bidirectional"))
    )
    (net (code "66") (name "unconnected-(DRIVER-CS7-Pad23)") (class "Default")
      (node (ref "DRIVER") (pin "23") (pinfunction "CS7_23") (pintype "bidirectional"))
    )
    (net (code "67") (name "unconnected-(DRIVER-CS8-Pad24)") (class "Default")
      (node (ref "DRIVER") (pin "24") (pinfunction "CS8_24") (pintype "bidirectional"))
    )
    (net (code "68") (name "unconnected-(DRIVER-CS9-Pad25)") (class "Default")
      (node (ref "DRIVER") (pin "25") (pinfunction "CS9_25") (pintype "bidirectional"))
    )
    (net (code "69") (name "unconnected-(DRIVER-CS10-Pad26)") (class "Default")
      (node (ref "DRIVER") (pin "26") (pinfunction "CS10_26") (pintype "bidirectional"))
    )
    (net (code "70") (name "unconnected-(DRIVER-CS11-Pad27)") (class "Default")
      (node (ref "DRIVER") (pin "27") (pinfunction "CS11_27") (pintype "bidirectional"))
    )
    (net (code "71") (name "unconnected-(DRIVER-CS12-Pad28)") (class "Default")
      (node (ref "DRIVER") (pin "28") (pinfunction "CS12_28") (pintype "bidirectional"))
    )
    (net (code "72") (name "unconnected-(DRIVER-CS13-Pad30)") (class "Default")
      (node (ref "DRIVER") (pin "30") (pinfunction "CS13_30") (pintype "bidirectional"))
    )
    (net (code "73") (name "unconnected-(DRIVER-CS14-Pad31)") (class "Default")
      (node (ref "DRIVER") (pin "31") (pinfunction "CS14_31") (pintype "bidirectional"))
    )
    (net (code "74") (name "unconnected-(DRIVER-CS15-Pad32)") (class "Default")
      (node (ref "DRIVER") (pin "32") (pinfunction "CS15_32") (pintype "bidirectional"))
    )
    (net (code "75") (name "unconnected-(DRIVER-CS16-Pad33)") (class "Default")
      (node (ref "DRIVER") (pin "33") (pinfunction "CS16_33") (pintype "bidirectional"))
    )
    (net (code "76") (name "unconnected-(DRIVER-INTB-Pad45)") (class "Default")
      (node (ref "DRIVER") (pin "45") (pinfunction "INTB_45") (pintype "bidirectional"))
    )
    (net (code "77") (name "unconnected-(DRIVER-NC_1-Pad1)") (class "Default")
      (node (ref "DRIVER") (pin "1") (pinfunction "NC_1_1") (pintype "bidirectional"))
    )
    (net (code "78") (name "unconnected-(DRIVER-NC_2-Pad36)") (class "Default")
      (node (ref "DRIVER") (pin "36") (pinfunction "NC_2_36") (pintype "bidirectional"))
    )
    (net (code "79") (name "unconnected-(DRIVER-SYNC-Pad40)") (class "Default")
      (node (ref "DRIVER") (pin "40") (pinfunction "SYNC_40") (pintype "bidirectional"))
    )
    (net (code "80") (name "unconnected-(J1-SBU1-PadA8)") (class "Default")
      (node (ref "J1") (pin "A8") (pinfunction "SBU1_A8") (pintype "bidirectional"))
    )
    (net (code "81") (name "unconnected-(J1-SBU2-PadB8)") (class "Default")
      (node (ref "J1") (pin "B8") (pinfunction "SBU2_B8") (pintype "bidirectional"))
    )
    (net (code "82") (name "unconnected-(MCU-AREF-Pad42)") (class "Default")
      (node (ref "MCU") (pin "42") (pinfunction "AREF_42") (pintype "bidirectional"))
    )
    (net (code "83") (name "unconnected-(MCU-PB0(SS{slash}PCINT0)-Pad8)") (class "Default")
      (node (ref "MCU") (pin "8") (pinfunction "PB0(SS/PCINT0)_8") (pintype "bidirectional"))
    )
    (net (code "84") (name "unconnected-(MCU-PB1(PCINT1{slash}SCLK)-Pad9)") (class "Default")
      (node (ref "MCU") (pin "9") (pinfunction "PB1(PCINT1/SCLK)_9") (pintype "bidirectional"))
    )
    (net (code "85") (name "unconnected-(MCU-PB2(PDI{slash}PCINT2{slash}MOSI)-Pad10)") (class "Default")
      (node (ref "MCU") (pin "10") (pinfunction "PB2(PDI/PCINT2/MOSI)_10") (pintype "bidirectional"))
    )
    (net (code "86") (name "unconnected-(MCU-PB7(PCINT7{slash}OC0A{slash}OC1C{slash}~{RTS})-Pad12)") (class "Default")
      (node (ref "MCU") (pin "12") (pinfunction "PB7(PCINT7/OC0A/OC1C/~{RTS})_12") (pintype "bidirectional"))
    )
    (net (code "87") (name "unconnected-(MCU-PD4(ICP1{slash}ADC8)-Pad25)") (class "Default")
      (node (ref "MCU") (pin "25") (pinfunction "PD4(ICP1/ADC8)_25") (pintype "bidirectional"))
    )
    (net (code "88") (name "unconnected-(MCU-PD5(XCLK1{slash}~{CTS})-Pad22)") (class "Default")
      (node (ref "MCU") (pin "22") (pinfunction "PD5(XCLK1/~{CTS})_22") (pintype "bidirectional"))
    )
    (net (code "89") (name "unconnected-(MCU-PE6(INT.6{slash}AIN0)-Pad1)") (class "Default")
      (node (ref "MCU") (pin "1") (pinfunction "PE6(INT.6/AIN0)_1") (pintype "bidirectional"))
    )
    (net (code "90") (name "unconnected-(MCU-PF0(ADC0)-Pad41)") (class "Default")
      (node (ref "MCU") (pin "41") (pinfunction "PF0(ADC0)_41") (pintype "bidirectional"))
    )
    (net (code "91") (name "unconnected-(MCU-PF1(ADC1)-Pad40)") (class "Default")
      (node (ref "MCU") (pin "40") (pinfunction "PF1(ADC1)_40") (pintype "bidirectional"))
    )
    (net (code "92") (name "unconnected-(MCU-PF4(ADC4{slash}TCK)-Pad39)") (class "Default")
      (node (ref "MCU") (pin "39") (pinfunction "PF4(ADC4/TCK)_39") (pintype "bidirectional"))
    )
    (net (code "93") (name "unconnected-(MCU-PF5(ADC5{slash}TMS)-Pad38)") (class "Default")
      (node (ref "MCU") (pin "38") (pinfunction "PF5(ADC5/TMS)_38") (pintype "bidirectional"))
    )
    (net (code "94") (name "unconnected-(MCU-PF6(ADC6{slash}TDO)-Pad37)") (class "Default")
      (node (ref "MCU") (pin "37") (pinfunction "PF6(ADC6/TDO)_37") (pintype "bidirectional"))
    )
    (net (code "95") (name "unconnected-(MCU-PF7(ADC7{slash}TDI)-Pad36)") (class "Default")
      (node (ref "MCU") (pin "36") (pinfunction "PF7(ADC7/TDI)_36") (pintype "bidirectional"))
    )
    (net (code "96") (name "unconnected-(UGLOW1-DOUT-PadP$2)") (class "Default")
      (node (ref "UGLOW1") (pin "P$2") (pinfunction "DOUT_P$2") (pintype "output"))
    )
  )
)
